# CBCM_PCB_Rev_1.net
KiCad netlist of a schematic drawn in Altium Designer
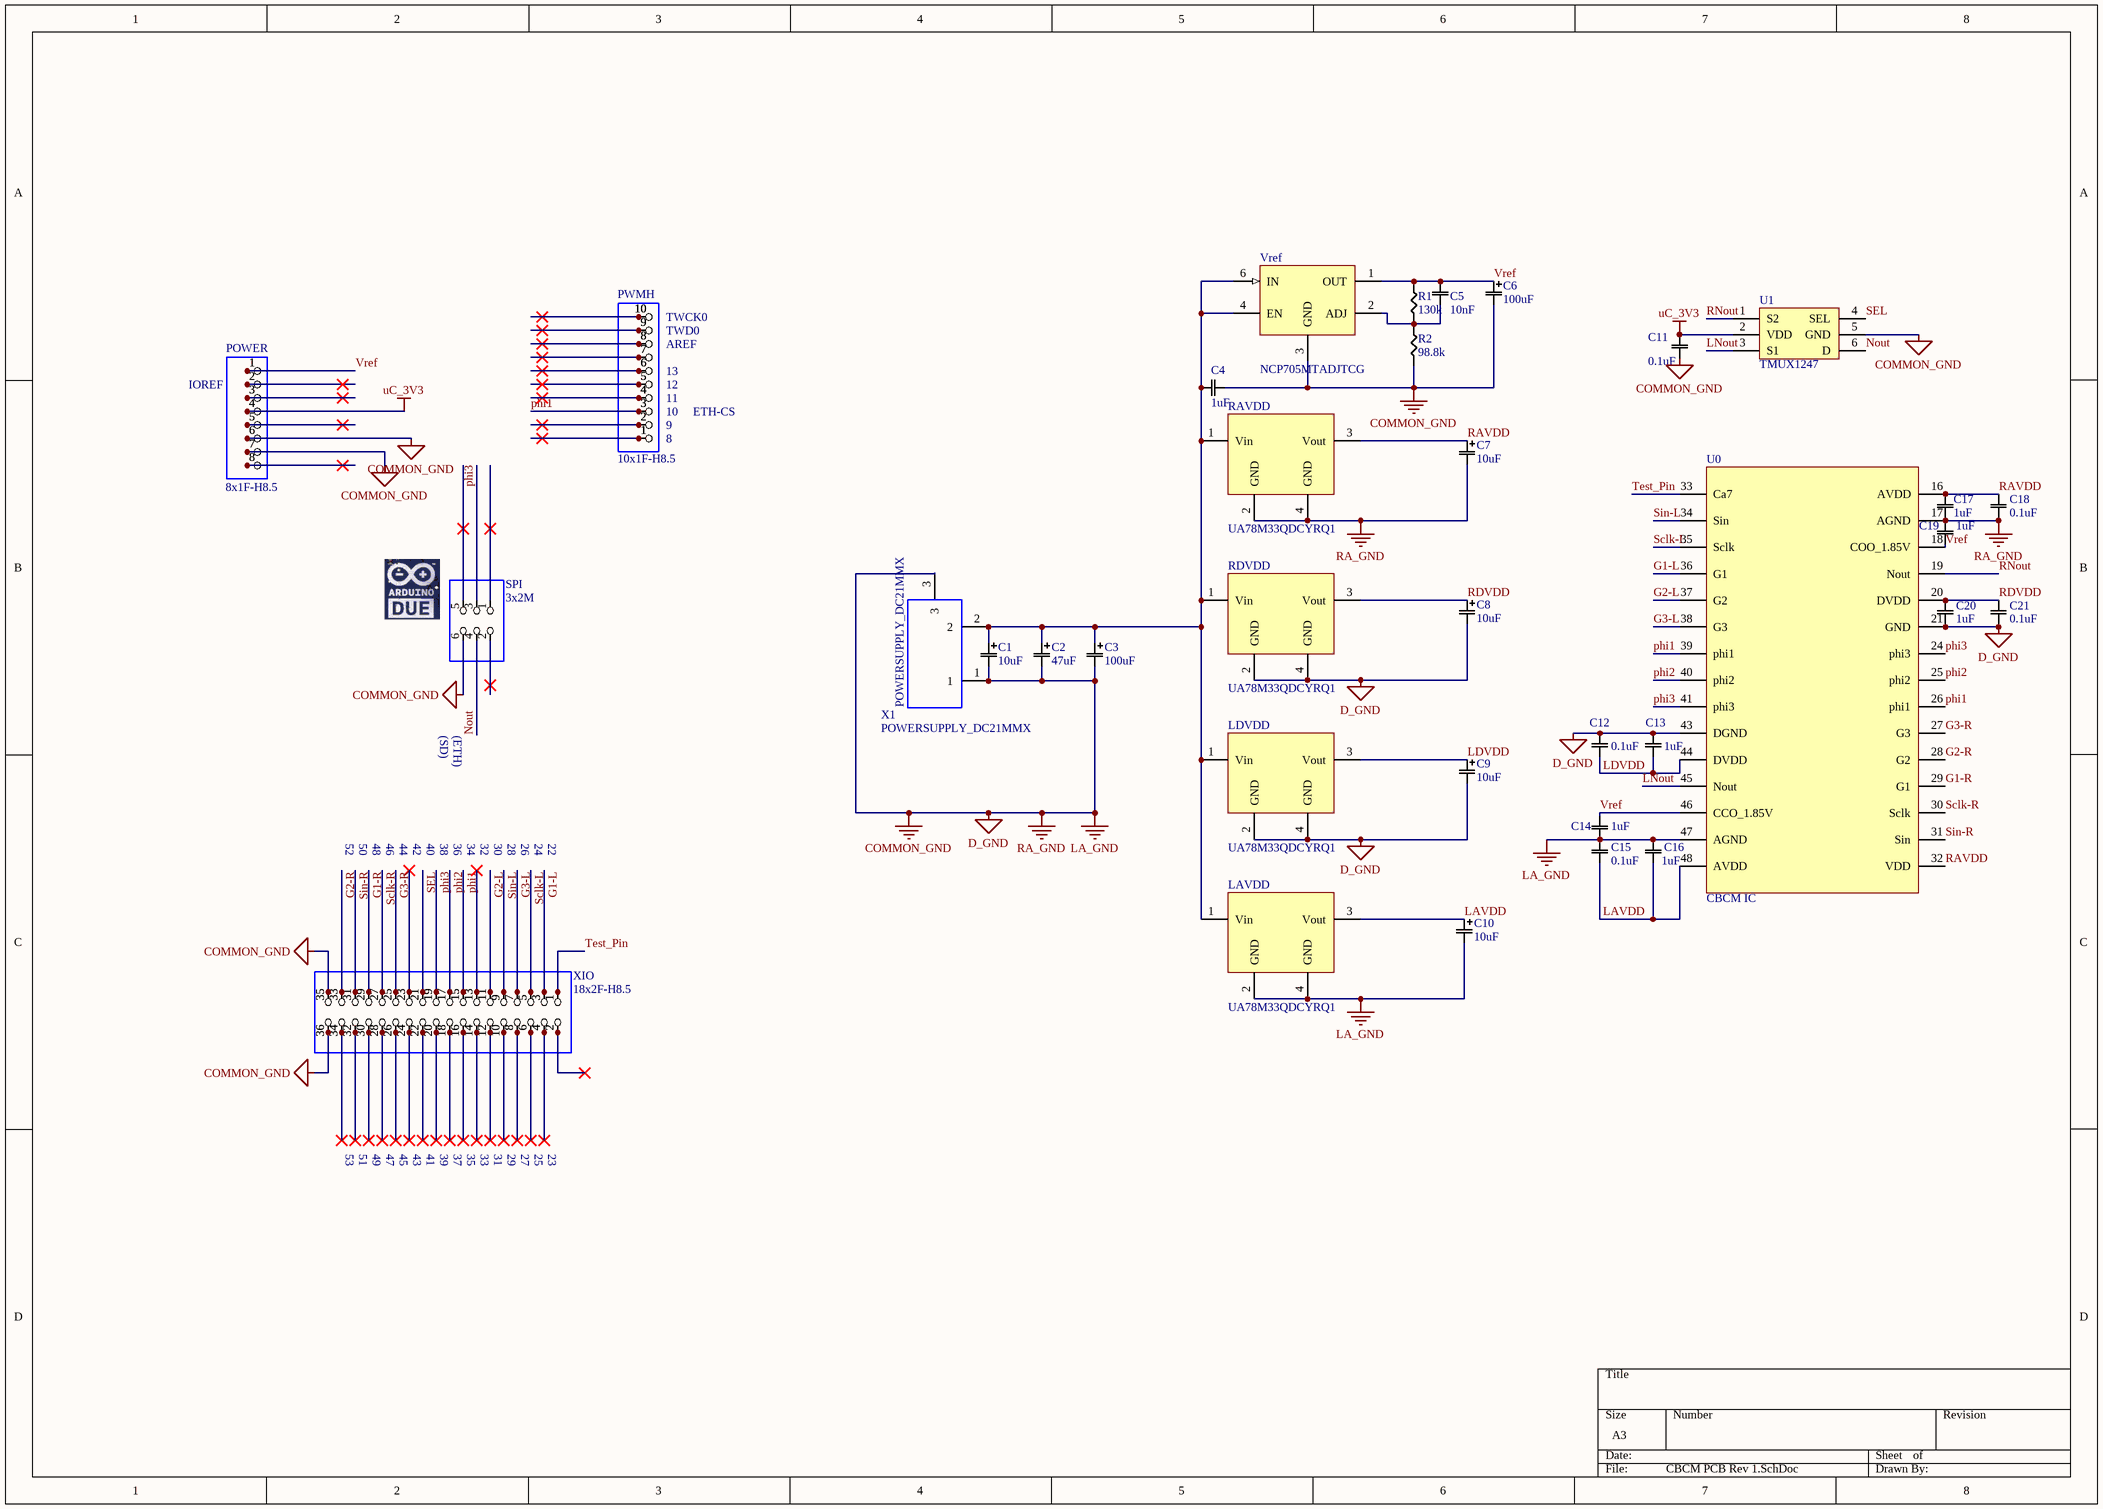
[diagram p0: CBCM PCB Rev 1.SchDoc]

(export (version "E")
  (design (tool "Eeschema 10.0.6"))
  (components
    (comp (ref "C1")
      (value "10uF")
      (footprint "CAPAE4643X55M")
      (libsource (lib "CBCM IC") (part "Electrolytic_CAP(4.0x5.5)"))
    )
    (comp (ref "C2")
      (value "47uF")
      (footprint "CAPAE4643X55M")
      (libsource (lib "CBCM IC") (part "Electrolytic_CAP(4.0x5.5)"))
    )
    (comp (ref "C3")
      (value "100uF")
      (footprint "CAPAE7066X77M")
      (libsource (lib "CBCM IC") (part "Electrolytic_CAP(6.3x7.7)"))
    )
    (comp (ref "C4") (value "1uF") (footprint "CAPC1608X09N") (libsource (lib "CBCM IC") (part "CAP0603")))
    (comp (ref "C5") (value "10nF") (footprint "CAPC1608X09N") (libsource (lib "CBCM IC") (part "CAP0603")))
    (comp (ref "C6")
      (value "100uF")
      (footprint "CAPAE7066X77M")
      (libsource (lib "CBCM IC") (part "Electrolytic_CAP(6.3x7.7)"))
    )
    (comp (ref "C7")
      (value "10uF")
      (footprint "CAPAE4643X55M")
      (libsource (lib "CBCM IC") (part "Electrolytic_CAP(4.0x5.5)"))
    )
    (comp (ref "C8")
      (value "10uF")
      (footprint "CAPAE4643X55M")
      (libsource (lib "CBCM IC") (part "Electrolytic_CAP(4.0x5.5)"))
    )
    (comp (ref "C9")
      (value "10uF")
      (footprint "CAPAE4643X55M")
      (libsource (lib "CBCM IC") (part "Electrolytic_CAP(4.0x5.5)"))
    )
    (comp (ref "C10")
      (value "10uF")
      (footprint "CAPAE4643X55M")
      (libsource (lib "CBCM IC") (part "Electrolytic_CAP(4.0x5.5)"))
    )
    (comp (ref "C11") (value "0.1uF") (footprint "CAPC1608X09N") (libsource (lib "CBCM IC") (part "CAP0603")))
    (comp (ref "C12") (value "0.1uF") (footprint "CAPC1608X09N") (libsource (lib "CBCM IC") (part "CAP0603")))
    (comp (ref "C13") (value "1uF") (footprint "CAPC1608X09N") (libsource (lib "CBCM IC") (part "CAP0603")))
    (comp (ref "C14") (value "1uF") (footprint "CAPC1608X09N") (libsource (lib "CBCM IC") (part "CAP0603")))
    (comp (ref "C15") (value "0.1uF") (footprint "CAPC1608X09N") (libsource (lib "CBCM IC") (part "CAP0603")))
    (comp (ref "C16") (value "1uF") (footprint "CAPC1608X09N") (libsource (lib "CBCM IC") (part "CAP0603")))
    (comp (ref "C17") (value "1uF") (footprint "CAPC1608X09N") (libsource (lib "CBCM IC") (part "CAP0603")))
    (comp (ref "C18") (value "0.1uF") (footprint "CAPC1608X09N") (libsource (lib "CBCM IC") (part "CAP0603")))
    (comp (ref "C19") (value "1uF") (footprint "CAPC1608X09N") (libsource (lib "CBCM IC") (part "CAP0603")))
    (comp (ref "C20") (value "1uF") (footprint "CAPC1608X09N") (libsource (lib "CBCM IC") (part "CAP0603")))
    (comp (ref "C21") (value "0.1uF") (footprint "CAPC1608X09N") (libsource (lib "CBCM IC") (part "CAP0603")))
    (comp (ref "LAVDD")
      (value "UA78M33QDCYRQ1")
      (footprint "SOT230P700X180-4N")
      (libsource (lib "CBCM IC") (part "UA78M33QDCYRQ1"))
    )
    (comp (ref "LDVDD")
      (value "UA78M33QDCYRQ1")
      (footprint "SOT230P700X180-4N")
      (libsource (lib "CBCM IC") (part "UA78M33QDCYRQ1"))
    )
    (comp (ref "POWER")
      (value "8x1F-H8.5")
      (footprint "1X08")
      (libsource (lib "SmartPrj") (part "PINHD-1X8"))
    )
    (comp (ref "PWMH")
      (value "10x1F-H8.5")
      (footprint "1X10")
      (libsource (lib "SmartPrj") (part "PINHD-1X10"))
    )
    (comp (ref "R1") (value "130k") (footprint "RESC1608X09N") (libsource (lib "CBCM IC") (part "RES0603")))
    (comp (ref "R2") (value "98.8k") (footprint "RESC1608X09N") (libsource (lib "CBCM IC") (part "RES0603")))
    (comp (ref "RAVDD")
      (value "UA78M33QDCYRQ1")
      (footprint "SOT230P700X180-4N")
      (libsource (lib "CBCM IC") (part "UA78M33QDCYRQ1"))
    )
    (comp (ref "RDVDD")
      (value "UA78M33QDCYRQ1")
      (footprint "SOT230P700X180-4N")
      (libsource (lib "CBCM IC") (part "UA78M33QDCYRQ1"))
    )
    (comp (ref "SPI") (value "3x2M") (footprint "2X03") (libsource (lib "SmartPrj") (part "PINHD-2X3")))
    (comp (ref "U0") (value "CBCM IC") (footprint "PGA85x11") (libsource (lib "CBCM IC") (part "CBCM IC")))
    (comp (ref "U1")
      (value "TMUX1247")
      (footprint "TSOP65P210X110-6N")
      (libsource (lib "CBCM IC") (part "TMUX1247"))
    )
    (comp (ref "Vref")
      (value "NCP705MTADJTCG")
      (footprint "WDFN6")
      (description "500 mA, Ultra-Low  Quiescent Current, IQ 13 A,  Ultra-Low Noise, LDO  Voltage Regulator")
      (fields (field (name "MANUFACTURER") "ON Semiconductor"))
      (libsource (lib "NCP705MTADJTCG") (part "NCP705MTADJTCG"))
    )
    (comp (ref "X1")
      (value "POWERSUPPLY_DC21MMX")
      (footprint "POWERSUPPLY_DC-21MM")
      (libsource (lib "Arduino_Due") (part "POWERSUPPLY_DC21MMX"))
    )
    (comp (ref "XIO")
      (value "18x2F-H8.5")
      (footprint "2X18")
      (libsource (lib "SmartPrj") (part "PINHD-2X18"))
    )
  )
  (nets
    (net (code "1") (name "/G1-L") (class "Default")
      (node (ref "U0") (pin "36") (pinfunction "G1_36") (pintype "passive"))
      (node (ref "XIO") (pin "3") (pinfunction "3_3") (pintype "passive"))
    )
    (net (code "2") (name "/G1-R") (class "Default")
      (node (ref "U0") (pin "29") (pinfunction "G1_29") (pintype "passive"))
      (node (ref "XIO") (pin "29") (pinfunction "29_29") (pintype "passive"))
    )
    (net (code "3") (name "/G2-L") (class "Default")
      (node (ref "U0") (pin "37") (pinfunction "G2_37") (pintype "passive"))
      (node (ref "XIO") (pin "11") (pinfunction "11_11") (pintype "passive"))
    )
    (net (code "4") (name "/G2-R") (class "Default")
      (node (ref "U0") (pin "28") (pinfunction "G2_28") (pintype "passive"))
      (node (ref "XIO") (pin "33") (pinfunction "33_33") (pintype "passive"))
    )
    (net (code "5") (name "/G3-L") (class "Default")
      (node (ref "U0") (pin "38") (pinfunction "G3_38") (pintype "passive"))
      (node (ref "XIO") (pin "7") (pinfunction "7_7") (pintype "passive"))
    )
    (net (code "6") (name "/G3-R") (class "Default")
      (node (ref "U0") (pin "27") (pinfunction "G3_27") (pintype "passive"))
      (node (ref "XIO") (pin "25") (pinfunction "25_25") (pintype "passive"))
    )
    (net (code "7") (name "/LAVDD") (class "Default")
      (node (ref "C10") (pin "1") (pinfunction "Terminal_0_1") (pintype "passive"))
      (node (ref "C15") (pin "1") (pinfunction "Terminal_0_1") (pintype "passive"))
      (node (ref "C16") (pin "1") (pinfunction "Terminal_0_1") (pintype "passive"))
      (node (ref "LAVDD") (pin "3") (pinfunction "Vout_3") (pintype "passive"))
      (node (ref "U0") (pin "48") (pinfunction "AVDD_48") (pintype "power_in"))
    )
    (net (code "8") (name "/LDVDD") (class "Default")
      (node (ref "C12") (pin "1") (pinfunction "Terminal_0_1") (pintype "passive"))
      (node (ref "C13") (pin "1") (pinfunction "Terminal_0_1") (pintype "passive"))
      (node (ref "C9") (pin "1") (pinfunction "Terminal_0_1") (pintype "passive"))
      (node (ref "LDVDD") (pin "3") (pinfunction "Vout_3") (pintype "passive"))
      (node (ref "U0") (pin "44") (pinfunction "DVDD_44") (pintype "power_in"))
    )
    (net (code "9") (name "/LNout") (class "Default")
      (node (ref "U0") (pin "45") (pinfunction "Nout_45") (pintype "passive"))
      (node (ref "U1") (pin "3") (pinfunction "S1_3") (pintype "passive"))
    )
    (net (code "10") (name "/Nout") (class "Default")
      (node (ref "SPI") (pin "4") (pinfunction "4_4") (pintype "passive"))
      (node (ref "U1") (pin "6") (pinfunction "D_6") (pintype "passive"))
    )
    (net (code "11") (name "/RAVDD") (class "Default")
      (node (ref "C17") (pin "2") (pinfunction "Terminal_2_2") (pintype "passive"))
      (node (ref "C18") (pin "2") (pinfunction "Terminal_2_2") (pintype "passive"))
      (node (ref "C7") (pin "1") (pinfunction "Terminal_0_1") (pintype "passive"))
      (node (ref "RAVDD") (pin "3") (pinfunction "Vout_3") (pintype "passive"))
      (node (ref "U0") (pin "16") (pinfunction "AVDD_16") (pintype "power_in"))
      (node (ref "U0") (pin "32") (pinfunction "VDD_32") (pintype "power_in"))
    )
    (net (code "12") (name "/RDVDD") (class "Default")
      (node (ref "C20") (pin "2") (pinfunction "Terminal_2_2") (pintype "passive"))
      (node (ref "C21") (pin "2") (pinfunction "Terminal_2_2") (pintype "passive"))
      (node (ref "C8") (pin "1") (pinfunction "Terminal_0_1") (pintype "passive"))
      (node (ref "RDVDD") (pin "3") (pinfunction "Vout_3") (pintype "passive"))
      (node (ref "U0") (pin "20") (pinfunction "DVDD_20") (pintype "power_in"))
    )
    (net (code "13") (name "/RNout") (class "Default")
      (node (ref "U0") (pin "19") (pinfunction "Nout_19") (pintype "passive"))
      (node (ref "U1") (pin "1") (pinfunction "S2_1") (pintype "passive"))
    )
    (net (code "14") (name "/SEL") (class "Default")
      (node (ref "U1") (pin "4") (pinfunction "SEL_4") (pintype "passive"))
      (node (ref "XIO") (pin "21") (pinfunction "21_21") (pintype "passive"))
    )
    (net (code "15") (name "/Sclk-L") (class "Default")
      (node (ref "U0") (pin "35") (pinfunction "Sclk_35") (pintype "passive"))
      (node (ref "XIO") (pin "5") (pinfunction "5_5") (pintype "passive"))
    )
    (net (code "16") (name "/Sclk-R") (class "Default")
      (node (ref "U0") (pin "30") (pinfunction "Sclk_30") (pintype "passive"))
      (node (ref "XIO") (pin "27") (pinfunction "27_27") (pintype "passive"))
    )
    (net (code "17") (name "/Sin-L") (class "Default")
      (node (ref "U0") (pin "34") (pinfunction "Sin_34") (pintype "passive"))
      (node (ref "XIO") (pin "9") (pinfunction "9_9") (pintype "passive"))
    )
    (net (code "18") (name "/Sin-R") (class "Default")
      (node (ref "U0") (pin "31") (pinfunction "Sin_31") (pintype "passive"))
      (node (ref "XIO") (pin "31") (pinfunction "31_31") (pintype "passive"))
    )
    (net (code "19") (name "/Test_Pin") (class "Default")
      (node (ref "U0") (pin "33") (pinfunction "Ca7_33") (pintype "passive"))
      (node (ref "XIO") (pin "1") (pinfunction "1_1") (pintype "passive"))
    )
    (net (code "20") (name "/Vref") (class "Default")
      (node (ref "C14") (pin "2") (pinfunction "Terminal_2_2") (pintype "passive"))
      (node (ref "C19") (pin "1") (pinfunction "Terminal_0_1") (pintype "passive"))
      (node (ref "C5") (pin "2") (pinfunction "Terminal_2_2") (pintype "passive"))
      (node (ref "C6") (pin "1") (pinfunction "Terminal_0_1") (pintype "passive"))
      (node (ref "POWER") (pin "1") (pinfunction "1_1") (pintype "passive"))
      (node (ref "R1") (pin "2") (pinfunction "Terminal_2_2") (pintype "passive"))
      (node (ref "U0") (pin "18") (pinfunction "COO_1.85V_18") (pintype "power_in"))
      (node (ref "U0") (pin "46") (pinfunction "CCO_1.85V_46") (pintype "power_in"))
      (node (ref "Vref") (pin "1") (pinfunction "OUT_1") (pintype "power_in"))
    )
    (net (code "21") (name "/phi1") (class "Default")
      (node (ref "PWMH") (pin "3") (pinfunction "3_3") (pintype "passive"))
      (node (ref "U0") (pin "26") (pinfunction "phi1_26") (pintype "passive"))
      (node (ref "U0") (pin "39") (pinfunction "phi1_39") (pintype "passive"))
      (node (ref "XIO") (pin "15") (pinfunction "15_15") (pintype "passive"))
    )
    (net (code "22") (name "/phi2") (class "Default")
      (node (ref "U0") (pin "25") (pinfunction "phi2_25") (pintype "passive"))
      (node (ref "U0") (pin "40") (pinfunction "phi2_40") (pintype "passive"))
      (node (ref "XIO") (pin "17") (pinfunction "17_17") (pintype "passive"))
    )
    (net (code "23") (name "/phi3") (class "Default")
      (node (ref "SPI") (pin "3") (pinfunction "3_3") (pintype "passive"))
      (node (ref "U0") (pin "24") (pinfunction "phi3_24") (pintype "passive"))
      (node (ref "U0") (pin "41") (pinfunction "phi3_41") (pintype "passive"))
      (node (ref "XIO") (pin "19") (pinfunction "19_19") (pintype "passive"))
    )
    (net (code "24") (name "COMMON_GND") (class "Default")
      (node (ref "C1") (pin "2") (pinfunction "Terminal_2_2") (pintype "passive"))
      (node (ref "C10") (pin "2") (pinfunction "Terminal_2_2") (pintype "passive"))
      (node (ref "C11") (pin "1") (pinfunction "Terminal_0_1") (pintype "passive"))
      (node (ref "C12") (pin "2") (pinfunction "Terminal_2_2") (pintype "passive"))
      (node (ref "C13") (pin "2") (pinfunction "Terminal_2_2") (pintype "passive"))
      (node (ref "C14") (pin "1") (pinfunction "Terminal_0_1") (pintype "passive"))
      (node (ref "C15") (pin "2") (pinfunction "Terminal_2_2") (pintype "passive"))
      (node (ref "C16") (pin "2") (pinfunction "Terminal_2_2") (pintype "passive"))
      (node (ref "C17") (pin "1") (pinfunction "Terminal_0_1") (pintype "passive"))
      (node (ref "C18") (pin "1") (pinfunction "Terminal_0_1") (pintype "passive"))
      (node (ref "C19") (pin "2") (pinfunction "Terminal_2_2") (pintype "passive"))
      (node (ref "C2") (pin "2") (pinfunction "Terminal_2_2") (pintype "passive"))
      (node (ref "C20") (pin "1") (pinfunction "Terminal_0_1") (pintype "passive"))
      (node (ref "C21") (pin "1") (pinfunction "Terminal_0_1") (pintype "passive"))
      (node (ref "C3") (pin "2") (pinfunction "Terminal_2_2") (pintype "passive"))
      (node (ref "C4") (pin "2") (pinfunction "Terminal_2_2") (pintype "passive"))
      (node (ref "C6") (pin "2") (pinfunction "Terminal_2_2") (pintype "passive"))
      (node (ref "C7") (pin "2") (pinfunction "Terminal_2_2") (pintype "passive"))
      (node (ref "C8") (pin "2") (pinfunction "Terminal_2_2") (pintype "passive"))
      (node (ref "C9") (pin "2") (pinfunction "Terminal_2_2") (pintype "passive"))
      (node (ref "LAVDD") (pin "2") (pinfunction "GND_2") (pintype "passive"))
      (node (ref "LAVDD") (pin "4") (pinfunction "GND_4") (pintype "passive"))
      (node (ref "LDVDD") (pin "2") (pinfunction "GND_2") (pintype "passive"))
      (node (ref "LDVDD") (pin "4") (pinfunction "GND_4") (pintype "passive"))
      (node (ref "POWER") (pin "6") (pinfunction "6_6") (pintype "passive"))
      (node (ref "POWER") (pin "7") (pinfunction "7_7") (pintype "passive"))
      (node (ref "R2") (pin "1") (pinfunction "Terminal_1_1") (pintype "passive"))
      (node (ref "RAVDD") (pin "2") (pinfunction "GND_2") (pintype "passive"))
      (node (ref "RAVDD") (pin "4") (pinfunction "GND_4") (pintype "passive"))
      (node (ref "RDVDD") (pin "2") (pinfunction "GND_2") (pintype "passive"))
      (node (ref "RDVDD") (pin "4") (pinfunction "GND_4") (pintype "passive"))
      (node (ref "SPI") (pin "6") (pinfunction "6_6") (pintype "passive"))
      (node (ref "U0") (pin "17") (pinfunction "AGND_17") (pintype "power_in"))
      (node (ref "U0") (pin "21") (pinfunction "GND_21") (pintype "power_in"))
      (node (ref "U0") (pin "43") (pinfunction "DGND_43") (pintype "passive"))
      (node (ref "U0") (pin "47") (pinfunction "AGND_47") (pintype "power_in"))
      (node (ref "U1") (pin "5") (pinfunction "GND_5") (pintype "passive"))
      (node (ref "Vref") (pin "3") (pinfunction "GND_3") (pintype "power_in"))
      (node (ref "X1") (pin "1") (pinfunction "1_1") (pintype "passive"))
      (node (ref "X1") (pin "3") (pinfunction "3_3") (pintype "passive"))
      (node (ref "XIO") (pin "35") (pinfunction "35_35") (pintype "passive"))
      (node (ref "XIO") (pin "36") (pinfunction "36_36") (pintype "passive"))
    )
    (net (code "25") (name "Net-(C1-Terminal_0)") (class "Default")
      (node (ref "C1") (pin "1") (pinfunction "Terminal_0_1") (pintype "passive"))
      (node (ref "C2") (pin "1") (pinfunction "Terminal_0_1") (pintype "passive"))
      (node (ref "C3") (pin "1") (pinfunction "Terminal_0_1") (pintype "passive"))
      (node (ref "C4") (pin "1") (pinfunction "Terminal_0_1") (pintype "passive"))
      (node (ref "LAVDD") (pin "1") (pinfunction "Vin_1") (pintype "passive"))
      (node (ref "LDVDD") (pin "1") (pinfunction "Vin_1") (pintype "passive"))
      (node (ref "RAVDD") (pin "1") (pinfunction "Vin_1") (pintype "passive"))
      (node (ref "RDVDD") (pin "1") (pinfunction "Vin_1") (pintype "passive"))
      (node (ref "Vref") (pin "4") (pinfunction "EN_4") (pintype "passive"))
      (node (ref "Vref") (pin "6") (pinfunction "IN_6") (pintype "input"))
      (node (ref "X1") (pin "2") (pinfunction "2_2") (pintype "power_in"))
    )
    (net (code "26") (name "Net-(C5-Terminal_0)") (class "Default")
      (node (ref "C5") (pin "1") (pinfunction "Terminal_0_1") (pintype "passive"))
      (node (ref "R1") (pin "1") (pinfunction "Terminal_1_1") (pintype "passive"))
      (node (ref "R2") (pin "2") (pinfunction "Terminal_2_2") (pintype "passive"))
      (node (ref "Vref") (pin "2") (pinfunction "ADJ_2") (pintype "passive"))
    )
    (net (code "27") (name "Net-(POWER-Pad2)") (class "Default")
      (node (ref "POWER") (pin "2") (pinfunction "2_2") (pintype "passive"))
    )
    (net (code "28") (name "Net-(POWER-Pad3)") (class "Default")
      (node (ref "POWER") (pin "3") (pinfunction "3_3") (pintype "passive"))
    )
    (net (code "29") (name "Net-(POWER-Pad5)") (class "Default")
      (node (ref "POWER") (pin "5") (pinfunction "5_5") (pintype "passive"))
    )
    (net (code "30") (name "Net-(POWER-Pad8)") (class "Default")
      (node (ref "POWER") (pin "8") (pinfunction "8_8") (pintype "passive"))
    )
    (net (code "31") (name "Net-(PWMH-Pad1)") (class "Default")
      (node (ref "PWMH") (pin "1") (pinfunction "1_1") (pintype "passive"))
    )
    (net (code "32") (name "Net-(PWMH-Pad2)") (class "Default")
      (node (ref "PWMH") (pin "2") (pinfunction "2_2") (pintype "passive"))
    )
    (net (code "33") (name "Net-(PWMH-Pad4)") (class "Default")
      (node (ref "PWMH") (pin "4") (pinfunction "4_4") (pintype "passive"))
    )
    (net (code "34") (name "Net-(PWMH-Pad5)") (class "Default")
      (node (ref "PWMH") (pin "5") (pinfunction "5_5") (pintype "passive"))
    )
    (net (code "35") (name "Net-(PWMH-Pad6)") (class "Default")
      (node (ref "PWMH") (pin "6") (pinfunction "6_6") (pintype "passive"))
    )
    (net (code "36") (name "Net-(PWMH-Pad7)") (class "Default")
      (node (ref "PWMH") (pin "7") (pinfunction "7_7") (pintype "passive"))
    )
    (net (code "37") (name "Net-(PWMH-Pad8)") (class "Default")
      (node (ref "PWMH") (pin "8") (pinfunction "8_8") (pintype "passive"))
    )
    (net (code "38") (name "Net-(PWMH-Pad9)") (class "Default")
      (node (ref "PWMH") (pin "9") (pinfunction "9_9") (pintype "passive"))
    )
    (net (code "39") (name "Net-(PWMH-Pad10)") (class "Default")
      (node (ref "PWMH") (pin "10") (pinfunction "10_10") (pintype "passive"))
    )
    (net (code "40") (name "uC_3V3") (class "Default")
      (node (ref "C11") (pin "2") (pinfunction "Terminal_2_2") (pintype "passive"))
      (node (ref "POWER") (pin "4") (pinfunction "4_4") (pintype "passive"))
      (node (ref "U1") (pin "2") (pinfunction "VDD_2") (pintype "passive"))
    )
    (net (code "41") (name "unconnected-(SPI-Pad1)") (class "Default")
      (node (ref "SPI") (pin "1") (pinfunction "1_1") (pintype "passive"))
    )
    (net (code "42") (name "unconnected-(SPI-Pad2)") (class "Default")
      (node (ref "SPI") (pin "2") (pinfunction "2_2") (pintype "passive"))
    )
    (net (code "43") (name "unconnected-(SPI-Pad5)") (class "Default")
      (node (ref "SPI") (pin "5") (pinfunction "5_5") (pintype "passive"))
    )
    (net (code "44") (name "unconnected-(XIO-Pad2)") (class "Default")
      (node (ref "XIO") (pin "2") (pinfunction "2_2") (pintype "passive+no_connect"))
    )
    (net (code "45") (name "unconnected-(XIO-Pad4)") (class "Default")
      (node (ref "XIO") (pin "4") (pinfunction "4_4") (pintype "passive+no_connect"))
    )
    (net (code "46") (name "unconnected-(XIO-Pad6)") (class "Default")
      (node (ref "XIO") (pin "6") (pinfunction "6_6") (pintype "passive+no_connect"))
    )
    (net (code "47") (name "unconnected-(XIO-Pad8)") (class "Default")
      (node (ref "XIO") (pin "8") (pinfunction "8_8") (pintype "passive+no_connect"))
    )
    (net (code "48") (name "unconnected-(XIO-Pad10)") (class "Default")
      (node (ref "XIO") (pin "10") (pinfunction "10_10") (pintype "passive+no_connect"))
    )
    (net (code "49") (name "unconnected-(XIO-Pad12)") (class "Default")
      (node (ref "XIO") (pin "12") (pinfunction "12_12") (pintype "passive+no_connect"))
    )
    (net (code "50") (name "unconnected-(XIO-Pad13)") (class "Default")
      (node (ref "XIO") (pin "13") (pinfunction "13_13") (pintype "passive+no_connect"))
    )
    (net (code "51") (name "unconnected-(XIO-Pad14)") (class "Default")
      (node (ref "XIO") (pin "14") (pinfunction "14_14") (pintype "passive+no_connect"))
    )
    (net (code "52") (name "unconnected-(XIO-Pad16)") (class "Default")
      (node (ref "XIO") (pin "16") (pinfunction "16_16") (pintype "passive+no_connect"))
    )
    (net (code "53") (name "unconnected-(XIO-Pad18)") (class "Default")
      (node (ref "XIO") (pin "18") (pinfunction "18_18") (pintype "passive+no_connect"))
    )
    (net (code "54") (name "unconnected-(XIO-Pad20)") (class "Default")
      (node (ref "XIO") (pin "20") (pinfunction "20_20") (pintype "passive+no_connect"))
    )
    (net (code "55") (name "unconnected-(XIO-Pad22)") (class "Default")
      (node (ref "XIO") (pin "22") (pinfunction "22_22") (pintype "passive+no_connect"))
    )
    (net (code "56") (name "unconnected-(XIO-Pad23)") (class "Default")
      (node (ref "XIO") (pin "23") (pinfunction "23_23") (pintype "passive+no_connect"))
    )
    (net (code "57") (name "unconnected-(XIO-Pad24)") (class "Default")
      (node (ref "XIO") (pin "24") (pinfunction "24_24") (pintype "passive+no_connect"))
    )
    (net (code "58") (name "unconnected-(XIO-Pad26)") (class "Default")
      (node (ref "XIO") (pin "26") (pinfunction "26_26") (pintype "passive+no_connect"))
    )
    (net (code "59") (name "unconnected-(XIO-Pad28)") (class "Default")
      (node (ref "XIO") (pin "28") (pinfunction "28_28") (pintype "passive+no_connect"))
    )
    (net (code "60") (name "unconnected-(XIO-Pad30)") (class "Default")
      (node (ref "XIO") (pin "30") (pinfunction "30_30") (pintype "passive+no_connect"))
    )
    (net (code "61") (name "unconnected-(XIO-Pad32)") (class "Default")
      (node (ref "XIO") (pin "32") (pinfunction "32_32") (pintype "passive+no_connect"))
    )
    (net (code "62") (name "unconnected-(XIO-Pad34)") (class "Default")
      (node (ref "XIO") (pin "34") (pinfunction "34_34") (pintype "passive+no_connect"))
    )
  )
)
